# PSD_Mount_v14.net
KiCad netlist of a schematic drawn in EAGLE
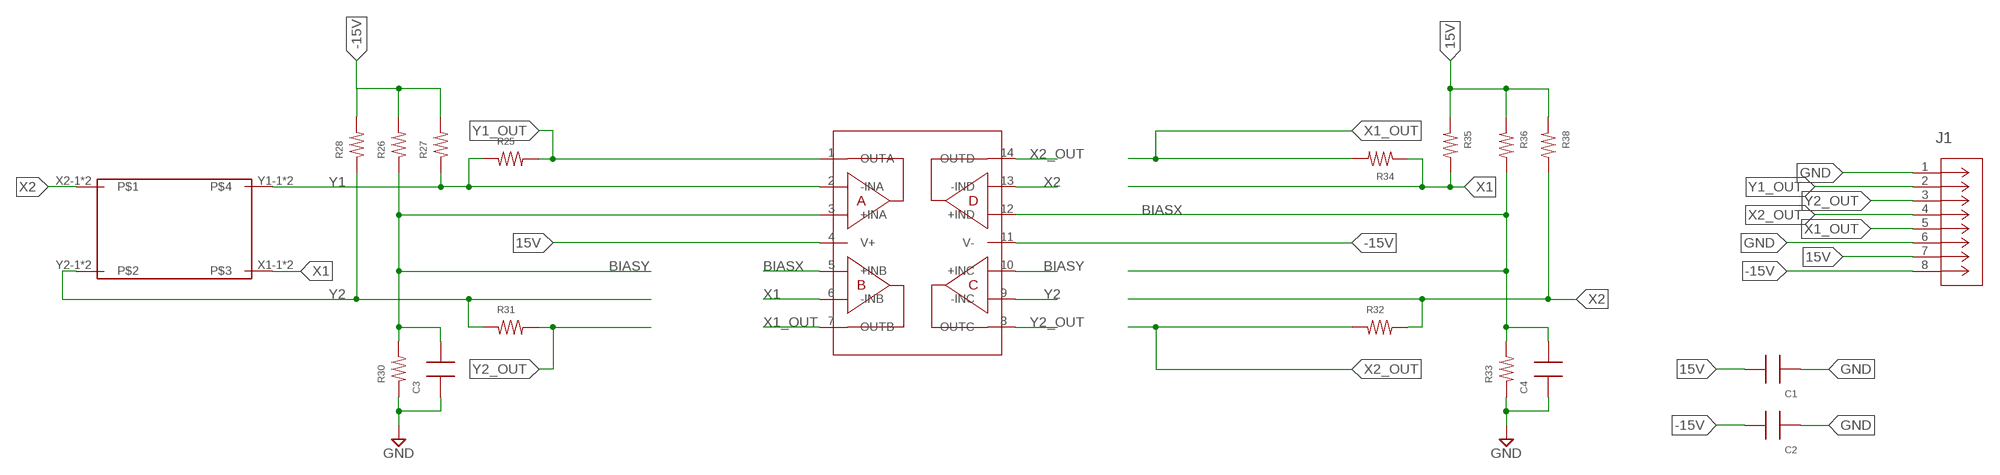
[diagram p0: schematic, sheet 1]

(export (version "E")
  (design (tool "Eeschema 10.0.6"))
  (components
    (comp (ref "AMP1")
      (value "OPA4140")
      (footprint "eagle-import:SOP65P640X120-14N")
      (libsource (lib "eagle-import") (part "OPA4140"))
    )
    (comp (ref "C1")
      (value "CAP0603")
      (footprint "eagle-import:0603")
      (libsource (lib "eagle-import") (part "CAP0603"))
    )
    (comp (ref "C2")
      (value "CAP0603")
      (footprint "eagle-import:0603")
      (libsource (lib "eagle-import") (part "CAP0603"))
    )
    (comp (ref "C3")
      (value "CAP0603")
      (footprint "eagle-import:0603")
      (libsource (lib "eagle-import") (part "CAP0603"))
    )
    (comp (ref "C4")
      (value "CAP0603")
      (footprint "eagle-import:0603")
      (libsource (lib "eagle-import") (part "CAP0603"))
    )
    (comp (ref "J1")
      (value "75869-332LF")
      (footprint "eagle-import:CONN_332LF_AMP")
      (fields (field (name "COPYRIGHT") "Copyright (C) 2018 Accelerated Designs. All rights reserved"))
      (libsource (lib "eagle-import") (part "75869-332LF"))
    )
    (comp (ref "R25")
      (value "RES0603")
      (footprint "eagle-import:0603")
      (libsource (lib "eagle-import") (part "RES0603"))
    )
    (comp (ref "R26")
      (value "RES0603")
      (footprint "eagle-import:0603")
      (libsource (lib "eagle-import") (part "RES0603"))
    )
    (comp (ref "R27")
      (value "RES0603")
      (footprint "eagle-import:0603")
      (libsource (lib "eagle-import") (part "RES0603"))
    )
    (comp (ref "R28")
      (value "RES0603")
      (footprint "eagle-import:0603")
      (libsource (lib "eagle-import") (part "RES0603"))
    )
    (comp (ref "R30")
      (value "RES0603")
      (footprint "eagle-import:0603")
      (libsource (lib "eagle-import") (part "RES0603"))
    )
    (comp (ref "R31")
      (value "RES0603")
      (footprint "eagle-import:0603")
      (libsource (lib "eagle-import") (part "RES0603"))
    )
    (comp (ref "R32")
      (value "RES0603")
      (footprint "eagle-import:0603")
      (libsource (lib "eagle-import") (part "RES0603"))
    )
    (comp (ref "R33")
      (value "RES0603")
      (footprint "eagle-import:0603")
      (libsource (lib "eagle-import") (part "RES0603"))
    )
    (comp (ref "R34")
      (value "RES0603")
      (footprint "eagle-import:0603")
      (libsource (lib "eagle-import") (part "RES0603"))
    )
    (comp (ref "R35")
      (value "RES0603")
      (footprint "eagle-import:0603")
      (libsource (lib "eagle-import") (part "RES0603"))
    )
    (comp (ref "R36")
      (value "RES0603")
      (footprint "eagle-import:0603")
      (libsource (lib "eagle-import") (part "RES0603"))
    )
    (comp (ref "R38")
      (value "RES0603")
      (footprint "eagle-import:0603")
      (libsource (lib "eagle-import") (part "RES0603"))
    )
    (comp (ref "U$1")
      (value "2L10UV_SU7")
      (footprint "eagle-import:2L10UV_SU7")
      (libsource (lib "eagle-import") (part "2L10UV_SU7"))
    )
  )
  (nets
    (net (code "1") (name "-15V") (class "Default")
      (node (ref "AMP1") (pin "11") (pinfunction "V-_11") (pintype "bidirectional"))
      (node (ref "C2") (pin "2") (pinfunction "P$2_2") (pintype "passive"))
      (node (ref "J1") (pin "8") (pinfunction "8_8") (pintype "passive"))
      (node (ref "R26") (pin "2") (pinfunction "P$2_2") (pintype "passive"))
      (node (ref "R27") (pin "2") (pinfunction "P$2_2") (pintype "passive"))
      (node (ref "R28") (pin "2") (pinfunction "P$2_2") (pintype "passive"))
    )
    (net (code "2") (name "/BIASX") (class "Default")
      (node (ref "AMP1") (pin "12") (pinfunction "+IND_12") (pintype "bidirectional"))
      (node (ref "AMP1") (pin "5") (pinfunction "+INB_5") (pintype "bidirectional"))
      (node (ref "C4") (pin "2") (pinfunction "P$2_2") (pintype "passive"))
      (node (ref "R33") (pin "2") (pinfunction "P$2_2") (pintype "passive"))
      (node (ref "R36") (pin "2") (pinfunction "P$2_2") (pintype "passive"))
    )
    (net (code "3") (name "/BIASY") (class "Default")
      (node (ref "AMP1") (pin "10") (pinfunction "+INC_10") (pintype "bidirectional"))
      (node (ref "AMP1") (pin "3") (pinfunction "+INA_3") (pintype "bidirectional"))
      (node (ref "C3") (pin "2") (pinfunction "P$2_2") (pintype "passive"))
      (node (ref "R26") (pin "1") (pinfunction "P$1_1") (pintype "passive"))
      (node (ref "R30") (pin "2") (pinfunction "P$2_2") (pintype "passive"))
    )
    (net (code "4") (name "/Y1") (class "Default")
      (node (ref "AMP1") (pin "2") (pinfunction "-INA_2") (pintype "bidirectional"))
      (node (ref "R25") (pin "1") (pinfunction "P$1_1") (pintype "passive"))
      (node (ref "R27") (pin "1") (pinfunction "P$1_1") (pintype "passive"))
      (node (ref "U$1") (pin "Y1-1") (pinfunction "P$4_Y1-1") (pintype "bidirectional"))
      (node (ref "U$1") (pin "Y1-2") (pinfunction "P$4_Y1-2") (pintype "bidirectional"))
    )
    (net (code "5") (name "/Y2") (class "Default")
      (node (ref "AMP1") (pin "9") (pinfunction "-INC_9") (pintype "bidirectional"))
      (node (ref "R28") (pin "1") (pinfunction "P$1_1") (pintype "passive"))
      (node (ref "R31") (pin "1") (pinfunction "P$1_1") (pintype "passive"))
      (node (ref "U$1") (pin "Y2-1") (pinfunction "P$2_Y2-1") (pintype "bidirectional"))
      (node (ref "U$1") (pin "Y2-2") (pinfunction "P$2_Y2-2") (pintype "bidirectional"))
    )
    (net (code "6") (name "15V") (class "Default")
      (node (ref "AMP1") (pin "4") (pinfunction "V+_4") (pintype "bidirectional"))
      (node (ref "C1") (pin "2") (pinfunction "P$2_2") (pintype "passive"))
      (node (ref "J1") (pin "7") (pinfunction "7_7") (pintype "passive"))
      (node (ref "R35") (pin "1") (pinfunction "P$1_1") (pintype "passive"))
      (node (ref "R36") (pin "1") (pinfunction "P$1_1") (pintype "passive"))
      (node (ref "R38") (pin "1") (pinfunction "P$1_1") (pintype "passive"))
    )
    (net (code "7") (name "GND") (class "Default")
      (node (ref "C1") (pin "1") (pinfunction "P$1_1") (pintype "passive"))
      (node (ref "C2") (pin "1") (pinfunction "P$1_1") (pintype "passive"))
      (node (ref "C3") (pin "1") (pinfunction "P$1_1") (pintype "passive"))
      (node (ref "C4") (pin "1") (pinfunction "P$1_1") (pintype "passive"))
      (node (ref "J1") (pin "1") (pinfunction "1_1") (pintype "passive"))
      (node (ref "J1") (pin "6") (pinfunction "6_6") (pintype "passive"))
      (node (ref "R30") (pin "1") (pinfunction "P$1_1") (pintype "passive"))
      (node (ref "R33") (pin "1") (pinfunction "P$1_1") (pintype "passive"))
    )
    (net (code "8") (name "X1") (class "Default")
      (node (ref "AMP1") (pin "6") (pinfunction "-INB_6") (pintype "bidirectional"))
      (node (ref "R34") (pin "1") (pinfunction "P$1_1") (pintype "passive"))
      (node (ref "R35") (pin "2") (pinfunction "P$2_2") (pintype "passive"))
      (node (ref "U$1") (pin "X1-1") (pinfunction "P$3_X1-1") (pintype "bidirectional"))
      (node (ref "U$1") (pin "X1-2") (pinfunction "P$3_X1-2") (pintype "bidirectional"))
    )
    (net (code "9") (name "X1_OUT") (class "Default")
      (node (ref "AMP1") (pin "7") (pinfunction "OUTB_7") (pintype "bidirectional"))
      (node (ref "J1") (pin "5") (pinfunction "5_5") (pintype "passive"))
      (node (ref "R34") (pin "2") (pinfunction "P$2_2") (pintype "passive"))
    )
    (net (code "10") (name "X2") (class "Default")
      (node (ref "AMP1") (pin "13") (pinfunction "-IND_13") (pintype "bidirectional"))
      (node (ref "R32") (pin "2") (pinfunction "P$2_2") (pintype "passive"))
      (node (ref "R38") (pin "2") (pinfunction "P$2_2") (pintype "passive"))
      (node (ref "U$1") (pin "X2-1") (pinfunction "P$1_X2-1") (pintype "bidirectional"))
      (node (ref "U$1") (pin "X2-2") (pinfunction "P$1_X2-2") (pintype "bidirectional"))
    )
    (net (code "11") (name "X2_OUT") (class "Default")
      (node (ref "AMP1") (pin "14") (pinfunction "OUTD_14") (pintype "bidirectional"))
      (node (ref "J1") (pin "4") (pinfunction "4_4") (pintype "passive"))
      (node (ref "R32") (pin "1") (pinfunction "P$1_1") (pintype "passive"))
    )
    (net (code "12") (name "Y1_OUT") (class "Default")
      (node (ref "AMP1") (pin "1") (pinfunction "OUTA_1") (pintype "bidirectional"))
      (node (ref "J1") (pin "2") (pinfunction "2_2") (pintype "passive"))
      (node (ref "R25") (pin "2") (pinfunction "P$2_2") (pintype "passive"))
    )
    (net (code "13") (name "Y2_OUT") (class "Default")
      (node (ref "AMP1") (pin "8") (pinfunction "OUTC_8") (pintype "bidirectional"))
      (node (ref "J1") (pin "3") (pinfunction "3_3") (pintype "passive"))
      (node (ref "R31") (pin "2") (pinfunction "P$2_2") (pintype "passive"))
    )
  )
)
